# altium_practice.net
KiCad netlist of a schematic drawn in Altium Designer
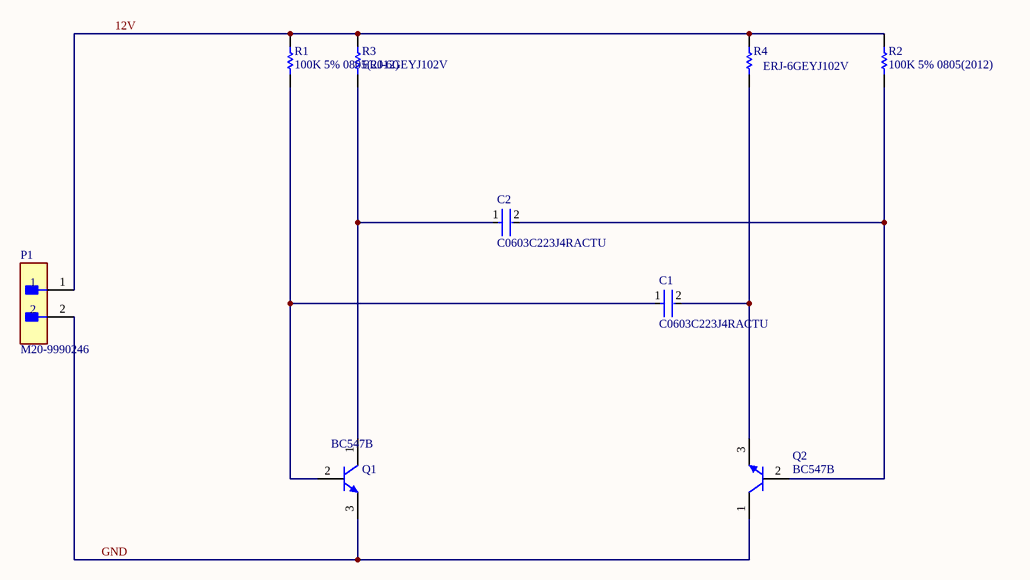
[diagram p0: altium_practice.SchDoc]

(export (version "E")
  (design (tool "Eeschema 10.0.6"))
  (components
    (comp (ref "C1")
      (value "C0603C223J4RACTU")
      (footprint "FP-C0603C-CF-MFG")
      (description "CAP CER 0.022UF 16V 5% X7R 0603")
      (fields
        (field (name "TOLERANCE") "0.05")
        (field (name "OCTOPART") "https://octopart.com/c0603c223j4ractu-kemet-12542861")
      )
      (libsource (lib "Altium Content Vault") (part "b4654b650e69147ec39a6b967a45e02"))
    )
    (comp (ref "C2")
      (value "C0603C223J4RACTU")
      (footprint "FP-C0603C-CF-MFG")
      (description "CAP CER 0.022UF 16V 5% X7R 0603")
      (fields
        (field (name "TOLERANCE") "0.05")
        (field (name "OCTOPART") "https://octopart.com/c0603c223j4ractu-kemet-12542861")
      )
      (libsource (lib "Altium Content Vault") (part "b4654b650e69147ec39a6b967a45e02"))
    )
    (comp (ref "P1")
      (value "M20-9990246")
      (footprint "FP-M20-9990246-MFG")
      (description "Connector Header Through Hole 2 position 0.100\" (2.54mm)")
      (fields (field (name "OCTOPART") "https://octopart.com/m20-9990246-harwin-2590635"))
      (libsource (lib "Altium Content Vault") (part "3bc925449376181038e59eaffc5286c"))
    )
    (comp (ref "Q1")
      (value "BC547B")
      (footprint "ONSC-TO-92-3-29-11")
      (description "Amplifier Transistor, NPN Silicon, 3-Pin TO-92, Bulk Box")
      (fields (field (name "MANUFACTURER") "On Semiconductor"))
      (libsource (lib "Altium Content Vault") (part "ONSC-NPN-C1B2E3-3"))
    )
    (comp (ref "Q2")
      (value "BC547B")
      (footprint "ONSC-TO-92-3-29-11")
      (description "Amplifier Transistor, NPN Silicon, 3-Pin TO-92, Bulk Box")
      (fields (field (name "MANUFACTURER") "On Semiconductor"))
      (libsource (lib "Altium Content Vault") (part "ONSC-NPN-C1B2E3-3"))
    )
    (comp (ref "R1")
      (value "100K 5% 0805(2012)")
      (footprint "RESC0805(2012)_L")
      (description "100K 0.125W 5% 0805 (2012 Metric)  SMD")
      (fields (field (name "TOLERANCE") "5 %") (field (name "POWER") "0.125 W"))
      (libsource (lib "Altium Content Vault") (part "RES"))
    )
    (comp (ref "R2")
      (value "100K 5% 0805(2012)")
      (footprint "RESC0805(2012)_L")
      (description "100K 0.125W 5% 0805 (2012 Metric)  SMD")
      (fields (field (name "TOLERANCE") "5 %") (field (name "POWER") "0.125 W"))
      (libsource (lib "Altium Content Vault") (part "RES"))
    )
    (comp (ref "R3")
      (value "ERJ-6GEYJ102V")
      (footprint "RESC2013X70X40ML20T20")
      (fields (field (name "MANUFACTURER") "Panasonic"))
      (libsource (lib "Altium Content Vault") (part "RES"))
    )
    (comp (ref "R4")
      (value "ERJ-6GEYJ102V")
      (footprint "RESC2013X70X40ML20T20")
      (fields (field (name "MANUFACTURER") "Panasonic"))
      (libsource (lib "Altium Content Vault") (part "RES"))
    )
  )
  (nets
    (net (code "1") (name "/12V") (class "Default")
      (node (ref "P1") (pin "1") (pinfunction "1_1") (pintype "passive"))
      (node (ref "R1") (pin "2") (pinfunction "2_2") (pintype "passive"))
      (node (ref "R2") (pin "2") (pinfunction "2_2") (pintype "passive"))
      (node (ref "R3") (pin "2") (pinfunction "2_2") (pintype "passive"))
      (node (ref "R4") (pin "2") (pinfunction "2_2") (pintype "passive"))
    )
    (net (code "2") (name "/GND") (class "Default")
      (node (ref "P1") (pin "2") (pinfunction "2_2") (pintype "passive"))
      (node (ref "Q1") (pin "3") (pinfunction "E_3") (pintype "passive"))
      (node (ref "Q2") (pin "1") (pinfunction "C_1") (pintype "passive"))
    )
    (net (code "3") (name "Net-(Q1-B)") (class "Default")
      (node (ref "C1") (pin "1") (pinfunction "1_1") (pintype "passive"))
      (node (ref "Q1") (pin "2") (pinfunction "B_2") (pintype "passive"))
      (node (ref "R1") (pin "1") (pinfunction "1_1") (pintype "passive"))
    )
    (net (code "4") (name "Net-(Q1-C)") (class "Default")
      (node (ref "C2") (pin "1") (pinfunction "1_1") (pintype "passive"))
      (node (ref "Q1") (pin "1") (pinfunction "C_1") (pintype "passive"))
      (node (ref "R3") (pin "1") (pinfunction "1_1") (pintype "passive"))
    )
    (net (code "5") (name "Net-(Q2-B)") (class "Default")
      (node (ref "C2") (pin "2") (pinfunction "2_2") (pintype "passive"))
      (node (ref "Q2") (pin "2") (pinfunction "B_2") (pintype "passive"))
      (node (ref "R2") (pin "1") (pinfunction "1_1") (pintype "passive"))
    )
    (net (code "6") (name "Net-(Q2-E)") (class "Default")
      (node (ref "C1") (pin "2") (pinfunction "2_2") (pintype "passive"))
      (node (ref "Q2") (pin "3") (pinfunction "E_3") (pintype "passive"))
      (node (ref "R4") (pin "1") (pinfunction "1_1") (pintype "passive"))
    )
  )
)
